# sch.net
KiCad netlist of a schematic drawn in Altium Designer
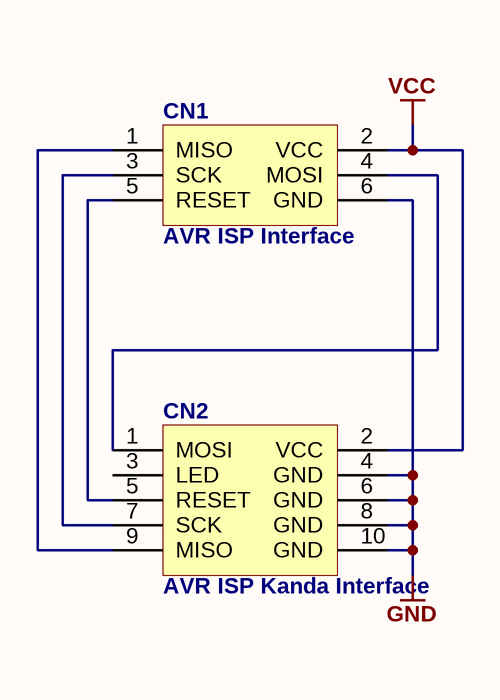
[diagram p0: sch.SchDoc]

(export (version "E")
  (design (tool "Eeschema 10.0.6"))
  (components
    (comp (ref "CN1")
      (value "AVR ISP Interface")
      (footprint "IDC6")
      (description "ISP Programming Header for AVR MCU's")
      (libsource (lib "mcu_prog_and_debug_connectors") (part "AVR ISP Interface"))
    )
    (comp (ref "CN2")
      (value "AVR ISP Kanda Interface")
      (footprint "GP_5x2H_F")
      (description "Kanda ISP Programming Header for AVR MCU's")
      (libsource (lib "mcu_prog_and_debug_connectors") (part "AVR ISP Kanda Interface"))
    )
  )
  (nets
    (net (code "1") (name "GND") (class "Default")
      (node (ref "CN1") (pin "6") (pinfunction "GND_6") (pintype "passive"))
      (node (ref "CN2") (pin "10") (pinfunction "GND_10") (pintype "passive"))
      (node (ref "CN2") (pin "4") (pinfunction "GND_4") (pintype "passive"))
      (node (ref "CN2") (pin "6") (pinfunction "GND_6") (pintype "passive"))
      (node (ref "CN2") (pin "8") (pinfunction "GND_8") (pintype "passive"))
    )
    (net (code "2") (name "Net-(CN1-MISO)") (class "Default")
      (node (ref "CN1") (pin "1") (pinfunction "MISO_1") (pintype "passive"))
      (node (ref "CN2") (pin "9") (pinfunction "MISO_9") (pintype "passive"))
    )
    (net (code "3") (name "Net-(CN1-MOSI)") (class "Default")
      (node (ref "CN1") (pin "4") (pinfunction "MOSI_4") (pintype "passive"))
      (node (ref "CN2") (pin "1") (pinfunction "MOSI_1") (pintype "passive"))
    )
    (net (code "4") (name "Net-(CN1-RESET)") (class "Default")
      (node (ref "CN1") (pin "5") (pinfunction "RESET_5") (pintype "passive"))
      (node (ref "CN2") (pin "5") (pinfunction "RESET_5") (pintype "passive"))
    )
    (net (code "5") (name "Net-(CN1-SCK)") (class "Default")
      (node (ref "CN1") (pin "3") (pinfunction "SCK_3") (pintype "passive"))
      (node (ref "CN2") (pin "7") (pinfunction "SCK_7") (pintype "passive"))
    )
    (net (code "6") (name "VCC") (class "Default")
      (node (ref "CN1") (pin "2") (pinfunction "VCC_2") (pintype "passive"))
      (node (ref "CN2") (pin "2") (pinfunction "VCC_2") (pintype "passive"))
    )
    (net (code "7") (name "unconnected-(CN2-LED-Pad3)") (class "Default")
      (node (ref "CN2") (pin "3") (pinfunction "LED_3") (pintype "passive"))
    )
  )
)
